# Sheet2.net
KiCad netlist of a schematic drawn in Altium Designer
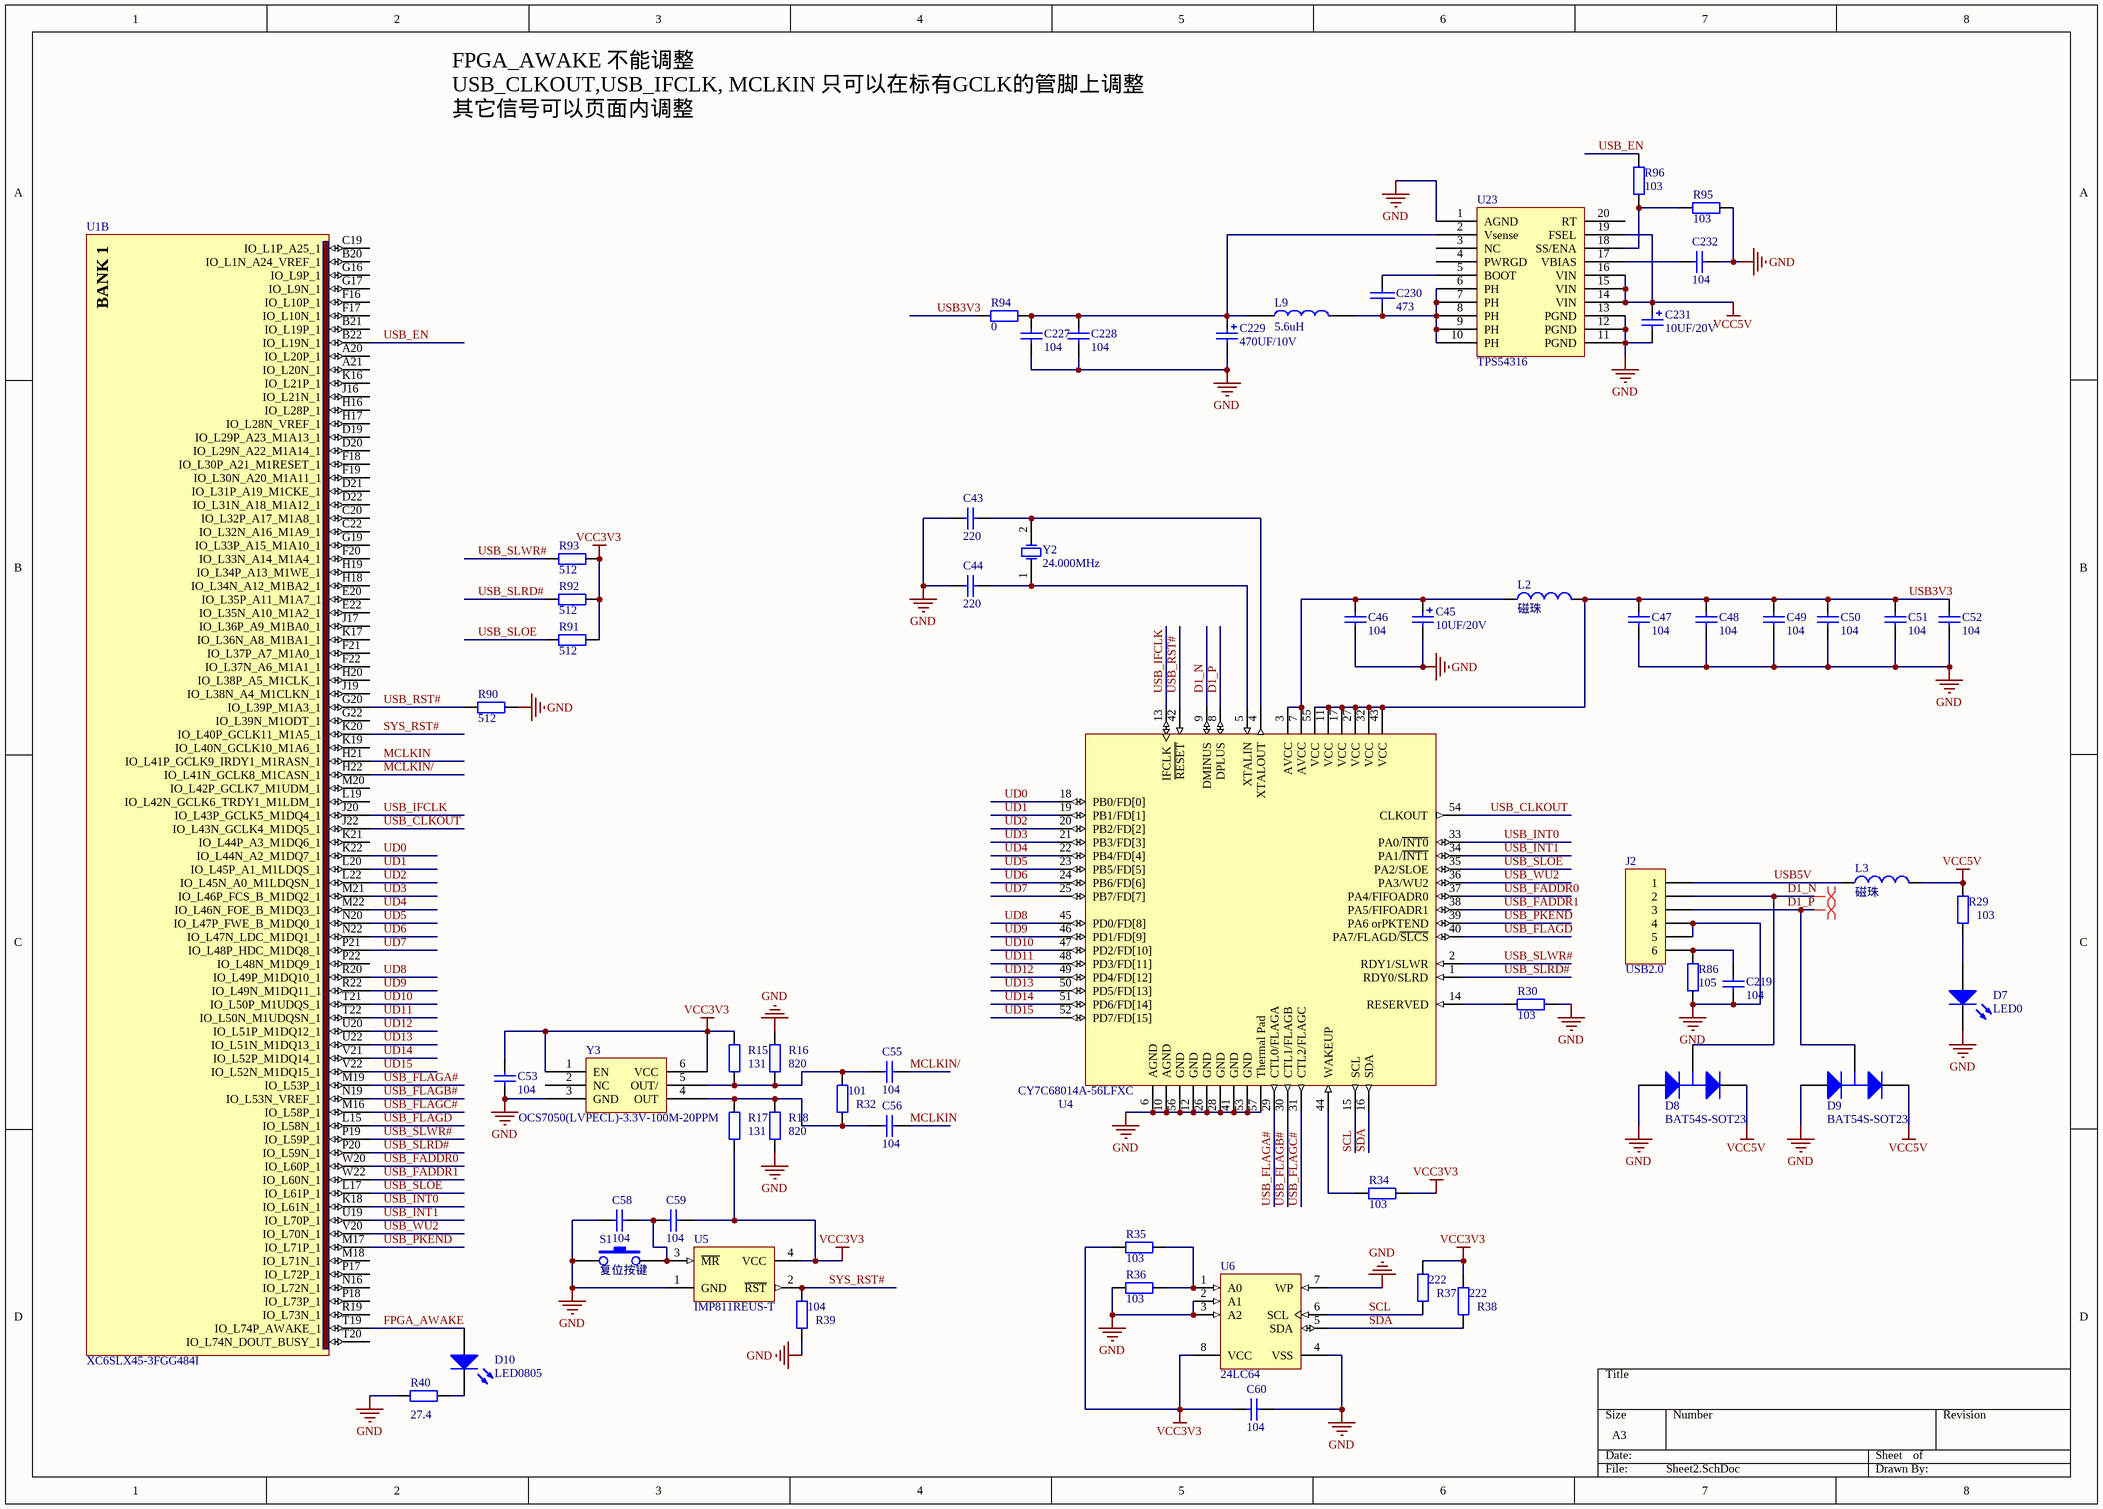
[diagram p0: Sheet2.SchDoc]

(export (version "E")
  (design (tool "Eeschema 10.0.6"))
  (components
    (comp (ref "C43")
      (value "220")
      (footprint "0402")
      (description "Capacitor")
      (fields (field (name "PUBLISHER") "Altium Limited"))
      (libsource (lib "Miscellaneous Devices") (part "Cap"))
    )
    (comp (ref "C44")
      (value "220")
      (footprint "0402")
      (description "Capacitor")
      (fields (field (name "PUBLISHER") "Altium Limited"))
      (libsource (lib "Miscellaneous Devices") (part "Cap"))
    )
    (comp (ref "C45")
      (value "10UF/20V")
      (footprint "CAP-B")
      (description "Polarized Capacitor (Axial)")
      (fields (field (name "PUBLISHER") "Altium Limited"))
      (libsource (lib "Miscellaneous Devices") (part "Cap Pol2"))
    )
    (comp (ref "C46")
      (value "104")
      (footprint "0402")
      (description "Capacitor")
      (fields (field (name "PUBLISHER") "Altium Limited"))
      (libsource (lib "Miscellaneous Devices") (part "Cap"))
    )
    (comp (ref "C47")
      (value "104")
      (footprint "0402")
      (description "Capacitor")
      (fields (field (name "PUBLISHER") "Altium Limited"))
      (libsource (lib "Miscellaneous Devices") (part "Cap"))
    )
    (comp (ref "C48")
      (value "104")
      (footprint "0402")
      (description "Capacitor")
      (fields (field (name "PUBLISHER") "Altium Limited"))
      (libsource (lib "Miscellaneous Devices") (part "Cap"))
    )
    (comp (ref "C49")
      (value "104")
      (footprint "0402")
      (description "Capacitor")
      (fields (field (name "PUBLISHER") "Altium Limited"))
      (libsource (lib "Miscellaneous Devices") (part "Cap"))
    )
    (comp (ref "C50")
      (value "104")
      (footprint "0402")
      (description "Capacitor")
      (fields (field (name "PUBLISHER") "Altium Limited"))
      (libsource (lib "Miscellaneous Devices") (part "Cap"))
    )
    (comp (ref "C51")
      (value "104")
      (footprint "0402")
      (description "Capacitor")
      (fields (field (name "PUBLISHER") "Altium Limited"))
      (libsource (lib "Miscellaneous Devices") (part "Cap"))
    )
    (comp (ref "C52")
      (value "104")
      (footprint "0402")
      (description "Capacitor")
      (fields (field (name "PUBLISHER") "Altium Limited"))
      (libsource (lib "Miscellaneous Devices") (part "Cap"))
    )
    (comp (ref "C53")
      (value "104")
      (footprint "0402")
      (description "Capacitor")
      (fields (field (name "PUBLISHER") "Altium Limited"))
      (libsource (lib "Miscellaneous Devices") (part "Cap"))
    )
    (comp (ref "C55")
      (value "104")
      (footprint "0402")
      (description "Capacitor")
      (fields (field (name "PUBLISHER") "Altium Limited"))
      (libsource (lib "Miscellaneous Devices") (part "Cap"))
    )
    (comp (ref "C56")
      (value "104")
      (footprint "0402")
      (description "Capacitor")
      (fields (field (name "PUBLISHER") "Altium Limited"))
      (libsource (lib "Miscellaneous Devices") (part "Cap"))
    )
    (comp (ref "C58")
      (value "104")
      (footprint "0402")
      (description "Capacitor")
      (fields (field (name "PUBLISHER") "Altium Limited"))
      (libsource (lib "Miscellaneous Devices") (part "Cap"))
    )
    (comp (ref "C59")
      (value "104")
      (footprint "0402")
      (description "Capacitor")
      (fields (field (name "PUBLISHER") "Altium Limited"))
      (libsource (lib "Miscellaneous Devices") (part "Cap"))
    )
    (comp (ref "C60")
      (value "104")
      (footprint "0402")
      (description "Capacitor")
      (fields (field (name "PUBLISHER") "Altium Limited"))
      (libsource (lib "Miscellaneous Devices") (part "Cap"))
    )
    (comp (ref "C219")
      (value "104")
      (footprint "0402")
      (description "Capacitor")
      (fields (field (name "PUBLISHER") "Altium Limited"))
      (libsource (lib "Miscellaneous Devices") (part "Cap"))
    )
    (comp (ref "C227")
      (value "104")
      (footprint "0402")
      (description "Capacitor")
      (fields (field (name "PUBLISHER") "Altium Limited"))
      (libsource (lib "Miscellaneous Devices") (part "Cap"))
    )
    (comp (ref "C228")
      (value "104")
      (footprint "0402")
      (description "Capacitor")
      (fields (field (name "PUBLISHER") "Altium Limited"))
      (libsource (lib "Miscellaneous Devices") (part "Cap"))
    )
    (comp (ref "C229")
      (value "470UF/10V")
      (footprint "CAP-D")
      (description "Polarized Capacitor (Axial)")
      (fields (field (name "PUBLISHER") "Altium Limited"))
      (libsource (lib "Miscellaneous Devices") (part "Cap Pol2"))
    )
    (comp (ref "C230")
      (value "473")
      (footprint "0402")
      (description "Capacitor")
      (libsource (lib "*") (part "CAP"))
    )
    (comp (ref "C231")
      (value "10UF/20V")
      (footprint "CAP-B")
      (description "Polarized Capacitor (Axial)")
      (fields (field (name "PUBLISHER") "Altium Limited"))
      (libsource (lib "Miscellaneous Devices") (part "Cap Pol2"))
    )
    (comp (ref "C232")
      (value "104")
      (footprint "0402")
      (description "Capacitor")
      (fields (field (name "PUBLISHER") "Altium Limited"))
      (libsource (lib "Miscellaneous Devices") (part "Cap"))
    )
    (comp (ref "D7")
      (value "LED0")
      (footprint "0805LED")
      (description "Typical INFRARED GaAs LED")
      (fields (field (name "PUBLISHER") "Altium Limited"))
      (libsource (lib "Miscellaneous Devices") (part "LED0"))
    )
    (comp (ref "D8")
      (value "BAT54S-SOT23")
      (footprint "SOT23-3L")
      (description "Silicon Switching Diode Array for High-Speed Switching")
      (fields (field (name "PUBLISHER") "Altium Limited"))
      (libsource (lib "Infineon Discrete Diode") (part "BAV99"))
    )
    (comp (ref "D9")
      (value "BAT54S-SOT23")
      (footprint "SOT23-3L")
      (description "Silicon Switching Diode Array for High-Speed Switching")
      (fields (field (name "PUBLISHER") "Altium Limited"))
      (libsource (lib "Infineon Discrete Diode") (part "BAV99"))
    )
    (comp (ref "D10")
      (value "LED0805")
      (footprint "0805LED")
      (description "Typical INFRARED GaAs LED")
      (fields (field (name "PUBLISHER") "Altium Limited"))
      (libsource (lib "Miscellaneous Devices") (part "LED0"))
    )
    (comp (ref "J2")
      (value "USB2.0")
      (footprint "USB/SM0.8-6H5")
      (description "Header, 6-Pin")
      (fields (field (name "PUBLISHER") "Altium Limited"))
      (libsource (lib "Miscellaneous Connectors") (part "Header 6"))
    )
    (comp (ref "L2")
      (value "磁珠")
      (footprint "1206A")
      (description "Inductor")
      (fields (field (name "PUBLISHER") "Altium Limited"))
      (libsource (lib "Miscellaneous Devices") (part "Inductor"))
    )
    (comp (ref "L3")
      (value "磁珠")
      (footprint "1206A")
      (description "Inductor")
      (fields (field (name "PUBLISHER") "Altium Limited"))
      (libsource (lib "Miscellaneous Devices") (part "Inductor"))
    )
    (comp (ref "L9") (value "5.6uH") (footprint "L5R2") (libsource (lib "*") (part "INDUCTOR1")))
    (comp (ref "R15")
      (value "131")
      (footprint "0603")
      (description "Resistor")
      (fields (field (name "PUBLISHER") "Altium Limited"))
      (libsource (lib "") (part "Res2_1"))
    )
    (comp (ref "R16")
      (value "820")
      (footprint "0603")
      (description "Resistor")
      (fields (field (name "PUBLISHER") "Altium Limited"))
      (libsource (lib "") (part "Res2_1"))
    )
    (comp (ref "R17")
      (value "131")
      (footprint "0603")
      (description "Resistor")
      (fields (field (name "PUBLISHER") "Altium Limited"))
      (libsource (lib "") (part "Res2_1"))
    )
    (comp (ref "R18")
      (value "820")
      (footprint "0603")
      (description "Resistor")
      (fields (field (name "PUBLISHER") "Altium Limited"))
      (libsource (lib "") (part "Res2_1"))
    )
    (comp (ref "R29")
      (value "103")
      (footprint "0603")
      (description "Resistor")
      (fields (field (name "PUBLISHER") "Altium Limited"))
      (libsource (lib "") (part "Res2_1"))
    )
    (comp (ref "R30")
      (value "103")
      (footprint "0603")
      (description "Resistor")
      (fields (field (name "PUBLISHER") "Altium Limited"))
      (libsource (lib "") (part "Res2_2"))
    )
    (comp (ref "R32")
      (value "101")
      (footprint "0603")
      (description "Resistor")
      (fields (field (name "PUBLISHER") "Altium Limited"))
      (libsource (lib "") (part "Res2_1"))
    )
    (comp (ref "R34")
      (value "103")
      (footprint "0603")
      (description "Resistor")
      (fields (field (name "PUBLISHER") "Altium Limited"))
      (libsource (lib "Miscellaneous Devices") (part "Res2"))
    )
    (comp (ref "R35")
      (value "103")
      (footprint "0603")
      (description "Resistor")
      (fields (field (name "PUBLISHER") "Altium Limited"))
      (libsource (lib "Miscellaneous Devices") (part "Res2"))
    )
    (comp (ref "R36")
      (value "103")
      (footprint "0603")
      (description "Resistor")
      (fields (field (name "PUBLISHER") "Altium Limited"))
      (libsource (lib "Miscellaneous Devices") (part "Res2"))
    )
    (comp (ref "R37")
      (value "222")
      (footprint "0603")
      (description "Resistor")
      (fields (field (name "PUBLISHER") "Altium Limited"))
      (libsource (lib "") (part "Res2_3"))
    )
    (comp (ref "R38")
      (value "222")
      (footprint "0603")
      (description "Resistor")
      (fields (field (name "PUBLISHER") "Altium Limited"))
      (libsource (lib "") (part "Res2_3"))
    )
    (comp (ref "R39")
      (value "104")
      (footprint "0603")
      (description "Resistor")
      (fields (field (name "PUBLISHER") "Altium Limited"))
      (libsource (lib "") (part "Res2_1"))
    )
    (comp (ref "R40")
      (value "27.4")
      (footprint "0603")
      (description "Resistor")
      (fields (field (name "PUBLISHER") "Altium Limited"))
      (libsource (lib "") (part "Res2_2"))
    )
    (comp (ref "R86")
      (value "105")
      (footprint "0603")
      (description "Resistor")
      (fields (field (name "PUBLISHER") "Altium Limited"))
      (libsource (lib "") (part "Res2_1"))
    )
    (comp (ref "R90")
      (value "512")
      (footprint "0603")
      (description "Resistor")
      (fields (field (name "PUBLISHER") "Altium Limited"))
      (libsource (lib "Miscellaneous Devices") (part "Res2"))
    )
    (comp (ref "R91")
      (value "512")
      (footprint "0603")
      (description "Resistor")
      (fields (field (name "PUBLISHER") "Altium Limited"))
      (libsource (lib "Miscellaneous Devices") (part "Res2"))
    )
    (comp (ref "R92")
      (value "512")
      (footprint "0603")
      (description "Resistor")
      (fields (field (name "PUBLISHER") "Altium Limited"))
      (libsource (lib "Miscellaneous Devices") (part "Res2"))
    )
    (comp (ref "R93")
      (value "512")
      (footprint "0603")
      (description "Resistor")
      (fields (field (name "PUBLISHER") "Altium Limited"))
      (libsource (lib "Miscellaneous Devices") (part "Res2"))
    )
    (comp (ref "R94")
      (value "0")
      (footprint "0603")
      (description "Resistor")
      (fields (field (name "PUBLISHER") "Altium Limited"))
      (libsource (lib "Miscellaneous Devices") (part "Res2"))
    )
    (comp (ref "R95")
      (value "103")
      (footprint "0603")
      (description "Resistor")
      (fields (field (name "PUBLISHER") "Altium Limited"))
      (libsource (lib "Miscellaneous Devices") (part "Res2"))
    )
    (comp (ref "R96")
      (value "103")
      (footprint "0603")
      (description "Resistor")
      (fields (field (name "PUBLISHER") "Altium Limited"))
      (libsource (lib "") (part "Res2_3"))
    )
    (comp (ref "S1") (value "复位按键") (footprint "RESETKEY") (libsource (lib "*") (part "SW-PB")))
    (comp (ref "U1")
      (value "XC6SLX45-3FGG484I")
      (footprint "FGG484")
      (fields (field (name "PUBLISHER") "Altium Limited"))
      (libsource (lib "Xilinx Spartan-6") (part "XC6SLX45-3FGG484I"))
    )
    (comp (ref "U4")
      (value "CY7C68014A-56LFXC")
      (footprint "LF56A_N")
      (fields (field (name "PUBLISHER") "Altium Limited"))
      (libsource (lib "Cypress USB High-Speed") (part "CY7C68014A-56LFXC"))
    )
    (comp (ref "U5")
      (value "IMP811REUS-T")
      (footprint "SOT-143")
      (description "4-Pin µP Voltage Monitors with Manual Reset Input")
      (fields (field (name "PUBLISHER") "Altium Limited"))
      (libsource (lib "Maxim Power Mgt Supervisory Circuit") (part "MAX811-EUS-T"))
    )
    (comp (ref "U6")
      (value "24LC64")
      (footprint "SMD8XX")
      (description "2Kbit, 400kHz, 2.5V, I2C Serial EEPROM, 8-Pin SOIC 150mil, Industrial Temperature")
      (fields (field (name "PUBLISHER") "Altium Limited"))
      (libsource (lib "Microchip Memory I2C Serial EEPROM") (part "24LC02B-I/SN"))
    )
    (comp (ref "U23")
      (value "TPS54316")
      (footprint "SOP20")
      (description "TPS54312")
      (libsource (lib "*") (part "TPS54312"))
    )
    (comp (ref "Y2")
      (value "24.000MHz")
      (footprint "CRYSTAL_2")
      (description "Crystal Oscillator")
      (fields (field (name "PUBLISHER") "Altium Limited"))
      (libsource (lib "Miscellaneous Devices") (part "XTAL"))
    )
    (comp (ref "Y3")
      (value "OCS7050(LVPECL)-3.3V-100M-20PPM")
      (footprint "100M_diff")
      (libsource (lib "Schlib1") (part "Component_1"))
    )
  )
  (nets
    (net (code "1") (name "/D1_N") (class "Default")
      (node (ref "D8") (pin "3") (pinfunction "C_3") (pintype "passive"))
      (node (ref "J2") (pin "2") (pinfunction "2_2") (pintype "passive"))
      (node (ref "U4") (pin "9") (pinfunction "DMINUS_9") (pintype "bidirectional"))
    )
    (net (code "2") (name "/D1_P") (class "Default")
      (node (ref "D9") (pin "3") (pinfunction "C_3") (pintype "passive"))
      (node (ref "J2") (pin "3") (pinfunction "3_3") (pintype "passive"))
      (node (ref "U4") (pin "8") (pinfunction "DPLUS_8") (pintype "bidirectional"))
    )
    (net (code "3") (name "/FPGA_AWAKE") (class "Default")
      (node (ref "D10") (pin "1") (pinfunction "A_1") (pintype "passive"))
      (node (ref "U1") (pin "T19") (pinfunction "IO_L74P_AWAKE_1_T19") (pintype "bidirectional"))
    )
    (net (code "4") (name "/MCLKIN") (class "Default")
      (node (ref "C56") (pin "2") (pinfunction "2_2") (pintype "passive"))
      (node (ref "U1") (pin "H21") (pinfunction "IO_L41P_GCLK9_IRDY1_M1RASN_1_H21") (pintype "bidirectional"))
    )
    (net (code "5") (name "/MCLKIN{slash}") (class "Default")
      (node (ref "C55") (pin "2") (pinfunction "2_2") (pintype "passive"))
      (node (ref "U1") (pin "H22") (pinfunction "IO_L41N_GCLK8_M1CASN_1_H22") (pintype "bidirectional"))
    )
    (net (code "6") (name "/SCL") (class "Default")
      (node (ref "R37") (pin "2") (pinfunction "2_2") (pintype "passive"))
      (node (ref "U4") (pin "15") (pinfunction "SCL_15") (pintype "output"))
      (node (ref "U6") (pin "6") (pinfunction "SCL_6") (pintype "input"))
    )
    (net (code "7") (name "/SDA") (class "Default")
      (node (ref "R38") (pin "2") (pinfunction "2_2") (pintype "passive"))
      (node (ref "U4") (pin "16") (pinfunction "SDA_16") (pintype "output"))
      (node (ref "U6") (pin "5") (pinfunction "SDA_5") (pintype "bidirectional"))
    )
    (net (code "8") (name "/SYS_RST#") (class "Default")
      (node (ref "R39") (pin "2") (pinfunction "2_2") (pintype "passive"))
      (node (ref "U1") (pin "K20") (pinfunction "IO_L40P_GCLK11_M1A5_1_K20") (pintype "bidirectional"))
      (node (ref "U5") (pin "2") (pinfunction "~{RST}_2") (pintype "output"))
    )
    (net (code "9") (name "/UD0") (class "Default")
      (node (ref "U1") (pin "K22") (pinfunction "IO_L44N_A2_M1DQ7_1_K22") (pintype "bidirectional"))
      (node (ref "U4") (pin "18") (pinfunction "PB0/FD[0]_18") (pintype "bidirectional"))
    )
    (net (code "10") (name "/UD1") (class "Default")
      (node (ref "U1") (pin "L20") (pinfunction "IO_L45P_A1_M1LDQS_1_L20") (pintype "bidirectional"))
      (node (ref "U4") (pin "19") (pinfunction "PB1/FD[1]_19") (pintype "bidirectional"))
    )
    (net (code "11") (name "/UD2") (class "Default")
      (node (ref "U1") (pin "L22") (pinfunction "IO_L45N_A0_M1LDQSN_1_L22") (pintype "bidirectional"))
      (node (ref "U4") (pin "20") (pinfunction "PB2/FD[2]_20") (pintype "bidirectional"))
    )
    (net (code "12") (name "/UD3") (class "Default")
      (node (ref "U1") (pin "M21") (pinfunction "IO_L46P_FCS_B_M1DQ2_1_M21") (pintype "bidirectional"))
      (node (ref "U4") (pin "21") (pinfunction "PB3/FD[3]_21") (pintype "bidirectional"))
    )
    (net (code "13") (name "/UD4") (class "Default")
      (node (ref "U1") (pin "M22") (pinfunction "IO_L46N_FOE_B_M1DQ3_1_M22") (pintype "bidirectional"))
      (node (ref "U4") (pin "22") (pinfunction "PB4/FD[4]_22") (pintype "bidirectional"))
    )
    (net (code "14") (name "/UD5") (class "Default")
      (node (ref "U1") (pin "N20") (pinfunction "IO_L47P_FWE_B_M1DQ0_1_N20") (pintype "bidirectional"))
      (node (ref "U4") (pin "23") (pinfunction "PB5/FD[5]_23") (pintype "bidirectional"))
    )
    (net (code "15") (name "/UD6") (class "Default")
      (node (ref "U1") (pin "N22") (pinfunction "IO_L47N_LDC_M1DQ1_1_N22") (pintype "bidirectional"))
      (node (ref "U4") (pin "24") (pinfunction "PB6/FD[6]_24") (pintype "bidirectional"))
    )
    (net (code "16") (name "/UD7") (class "Default")
      (node (ref "U1") (pin "P21") (pinfunction "IO_L48P_HDC_M1DQ8_1_P21") (pintype "bidirectional"))
      (node (ref "U4") (pin "25") (pinfunction "PB7/FD[7]_25") (pintype "bidirectional"))
    )
    (net (code "17") (name "/UD8") (class "Default")
      (node (ref "U1") (pin "R20") (pinfunction "IO_L49P_M1DQ10_1_R20") (pintype "bidirectional"))
      (node (ref "U4") (pin "45") (pinfunction "PD0/FD[8]_45") (pintype "bidirectional"))
    )
    (net (code "18") (name "/UD9") (class "Default")
      (node (ref "U1") (pin "R22") (pinfunction "IO_L49N_M1DQ11_1_R22") (pintype "bidirectional"))
      (node (ref "U4") (pin "46") (pinfunction "PD1/FD[9]_46") (pintype "bidirectional"))
    )
    (net (code "19") (name "/UD10") (class "Default")
      (node (ref "U1") (pin "T21") (pinfunction "IO_L50P_M1UDQS_1_T21") (pintype "bidirectional"))
      (node (ref "U4") (pin "47") (pinfunction "PD2/FD[10]_47") (pintype "bidirectional"))
    )
    (net (code "20") (name "/UD11") (class "Default")
      (node (ref "U1") (pin "T22") (pinfunction "IO_L50N_M1UDQSN_1_T22") (pintype "bidirectional"))
      (node (ref "U4") (pin "48") (pinfunction "PD3/FD[11]_48") (pintype "bidirectional"))
    )
    (net (code "21") (name "/UD12") (class "Default")
      (node (ref "U1") (pin "U20") (pinfunction "IO_L51P_M1DQ12_1_U20") (pintype "bidirectional"))
      (node (ref "U4") (pin "49") (pinfunction "PD4/FD[12]_49") (pintype "bidirectional"))
    )
    (net (code "22") (name "/UD13") (class "Default")
      (node (ref "U1") (pin "U22") (pinfunction "IO_L51N_M1DQ13_1_U22") (pintype "bidirectional"))
      (node (ref "U4") (pin "50") (pinfunction "PD5/FD[13]_50") (pintype "bidirectional"))
    )
    (net (code "23") (name "/UD14") (class "Default")
      (node (ref "U1") (pin "V21") (pinfunction "IO_L52P_M1DQ14_1_V21") (pintype "bidirectional"))
      (node (ref "U4") (pin "51") (pinfunction "PD6/FD[14]_51") (pintype "bidirectional"))
    )
    (net (code "24") (name "/UD15") (class "Default")
      (node (ref "U1") (pin "V22") (pinfunction "IO_L52N_M1DQ15_1_V22") (pintype "bidirectional"))
      (node (ref "U4") (pin "52") (pinfunction "PD7/FD[15]_52") (pintype "bidirectional"))
    )
    (net (code "25") (name "/USB3V3") (class "Default")
      (node (ref "C47") (pin "2") (pinfunction "2_2") (pintype "passive"))
      (node (ref "C48") (pin "2") (pinfunction "2_2") (pintype "passive"))
      (node (ref "C49") (pin "2") (pinfunction "2_2") (pintype "passive"))
      (node (ref "C50") (pin "2") (pinfunction "2_2") (pintype "passive"))
      (node (ref "C51") (pin "2") (pinfunction "2_2") (pintype "passive"))
      (node (ref "C52") (pin "2") (pinfunction "2_2") (pintype "passive"))
      (node (ref "L2") (pin "2") (pinfunction "2_2") (pintype "passive"))
      (node (ref "R94") (pin "2") (pinfunction "2_2") (pintype "passive"))
      (node (ref "U4") (pin "11") (pinfunction "VCC_11") (pintype "power_in"))
      (node (ref "U4") (pin "17") (pinfunction "VCC_17") (pintype "power_in"))
      (node (ref "U4") (pin "27") (pinfunction "VCC_27") (pintype "power_in"))
      (node (ref "U4") (pin "32") (pinfunction "VCC_32") (pintype "power_in"))
      (node (ref "U4") (pin "43") (pinfunction "VCC_43") (pintype "power_in"))
      (node (ref "U4") (pin "55") (pinfunction "VCC_55") (pintype "power_in"))
    )
    (net (code "26") (name "/USB5V") (class "Default")
      (node (ref "J2") (pin "1") (pinfunction "1_1") (pintype "passive"))
      (node (ref "L3") (pin "1") (pinfunction "1_1") (pintype "passive"))
    )
    (net (code "27") (name "/USB_CLKOUT") (class "Default")
      (node (ref "U1") (pin "J22") (pinfunction "IO_L43N_GCLK4_M1DQ5_1_J22") (pintype "bidirectional"))
      (node (ref "U4") (pin "54") (pinfunction "CLKOUT_54") (pintype "output"))
    )
    (net (code "28") (name "/USB_EN") (class "Default")
      (node (ref "R96") (pin "1") (pinfunction "1_1") (pintype "passive"))
      (node (ref "U1") (pin "B22") (pinfunction "IO_L19N_1_B22") (pintype "bidirectional"))
    )
    (net (code "29") (name "/USB_FADDR0") (class "Default")
      (node (ref "U1") (pin "W20") (pinfunction "IO_L60P_1_W20") (pintype "bidirectional"))
      (node (ref "U4") (pin "37") (pinfunction "PA4/FIFOADR0_37") (pintype "bidirectional"))
    )
    (net (code "30") (name "/USB_FADDR1") (class "Default")
      (node (ref "U1") (pin "W22") (pinfunction "IO_L60N_1_W22") (pintype "bidirectional"))
      (node (ref "U4") (pin "38") (pinfunction "PA5/FIFOADR1_38") (pintype "bidirectional"))
    )
    (net (code "31") (name "/USB_FLAGA#") (class "Default")
      (node (ref "U1") (pin "M19") (pinfunction "IO_L53P_1_M19") (pintype "bidirectional"))
      (node (ref "U4") (pin "29") (pinfunction "CTL0/FLAGA_29") (pintype "output"))
    )
    (net (code "32") (name "/USB_FLAGB#") (class "Default")
      (node (ref "U1") (pin "N19") (pinfunction "IO_L53N_VREF_1_N19") (pintype "bidirectional"))
      (node (ref "U4") (pin "30") (pinfunction "CTL1/FLAGB_30") (pintype "output"))
    )
    (net (code "33") (name "/USB_FLAGC#") (class "Default")
      (node (ref "U1") (pin "M16") (pinfunction "IO_L58P_1_M16") (pintype "bidirectional"))
      (node (ref "U4") (pin "31") (pinfunction "CTL2/FLAGC_31") (pintype "output"))
    )
    (net (code "34") (name "/USB_FLAGD") (class "Default")
      (node (ref "U1") (pin "L15") (pinfunction "IO_L58N_1_L15") (pintype "bidirectional"))
      (node (ref "U4") (pin "40") (pinfunction "PA7/FLAGD/~{SLCS}_40") (pintype "bidirectional"))
    )
    (net (code "35") (name "/USB_IFCLK") (class "Default")
      (node (ref "U1") (pin "J20") (pinfunction "IO_L43P_GCLK5_M1DQ4_1_J20") (pintype "bidirectional"))
      (node (ref "U4") (pin "13") (pinfunction "IFCLK_13") (pintype "bidirectional"))
    )
    (net (code "36") (name "/USB_INT0") (class "Default")
      (node (ref "U1") (pin "K18") (pinfunction "IO_L61N_1_K18") (pintype "bidirectional"))
      (node (ref "U4") (pin "33") (pinfunction "PA0/~{INT0}_33") (pintype "bidirectional"))
    )
    (net (code "37") (name "/USB_INT1") (class "Default")
      (node (ref "U1") (pin "U19") (pinfunction "IO_L70P_1_U19") (pintype "bidirectional"))
      (node (ref "U4") (pin "34") (pinfunction "PA1/~{INT1}_34") (pintype "bidirectional"))
    )
    (net (code "38") (name "/USB_PKEND") (class "Default")
      (node (ref "U1") (pin "M17") (pinfunction "IO_L71P_1_M17") (pintype "bidirectional"))
      (node (ref "U4") (pin "39") (pinfunction "PA6_orPKTEND_39") (pintype "bidirectional"))
    )
    (net (code "39") (name "/USB_RST#") (class "Default")
      (node (ref "R90") (pin "2") (pinfunction "2_2") (pintype "passive"))
      (node (ref "U1") (pin "G20") (pinfunction "IO_L39P_M1A3_1_G20") (pintype "bidirectional"))
      (node (ref "U4") (pin "42") (pinfunction "~{RESET}_42") (pintype "input"))
    )
    (net (code "40") (name "/USB_SLOE") (class "Default")
      (node (ref "R91") (pin "2") (pinfunction "2_2") (pintype "passive"))
      (node (ref "U1") (pin "L17") (pinfunction "IO_L61P_1_L17") (pintype "bidirectional"))
      (node (ref "U4") (pin "35") (pinfunction "PA2/SLOE_35") (pintype "bidirectional"))
    )
    (net (code "41") (name "/USB_SLRD#") (class "Default")
      (node (ref "R92") (pin "2") (pinfunction "2_2") (pintype "passive"))
      (node (ref "U1") (pin "P20") (pinfunction "IO_L59N_1_P20") (pintype "bidirectional"))
      (node (ref "U4") (pin "1") (pinfunction "RDY0/SLRD_1") (pintype "input"))
    )
    (net (code "42") (name "/USB_SLWR#") (class "Default")
      (node (ref "R93") (pin "2") (pinfunction "2_2") (pintype "passive"))
      (node (ref "U1") (pin "P19") (pinfunction "IO_L59P_1_P19") (pintype "bidirectional"))
      (node (ref "U4") (pin "2") (pinfunction "RDY1/SLWR_2") (pintype "input"))
    )
    (net (code "43") (name "/USB_WU2") (class "Default")
      (node (ref "U1") (pin "V20") (pinfunction "IO_L70N_1_V20") (pintype "bidirectional"))
      (node (ref "U4") (pin "36") (pinfunction "PA3/WU2_36") (pintype "bidirectional"))
    )
    (net (code "44") (name "GND") (class "Default")
      (node (ref "C219") (pin "2") (pinfunction "2_2") (pintype "passive"))
      (node (ref "C227") (pin "1") (pinfunction "1_1") (pintype "passive"))
      (node (ref "C228") (pin "1") (pinfunction "1_1") (pintype "passive"))
      (node (ref "C229") (pin "2") (pinfunction "2_2") (pintype "passive"))
      (node (ref "C231") (pin "2") (pinfunction "2_2") (pintype "passive"))
      (node (ref "C232") (pin "1") (pinfunction "1_1") (pintype "passive"))
      (node (ref "C43") (pin "1") (pinfunction "1_1") (pintype "passive"))
      (node (ref "C44") (pin "1") (pinfunction "1_1") (pintype "passive"))
      (node (ref "C45") (pin "2") (pinfunction "2_2") (pintype "passive"))
      (node (ref "C46") (pin "1") (pinfunction "1_1") (pintype "passive"))
      (node (ref "C47") (pin "1") (pinfunction "1_1") (pintype "passive"))
      (node (ref "C48") (pin "1") (pinfunction "1_1") (pintype "passive"))
      (node (ref "C49") (pin "1") (pinfunction "1_1") (pintype "passive"))
      (node (ref "C50") (pin "1") (pinfunction "1_1") (pintype "passive"))
      (node (ref "C51") (pin "1") (pinfunction "1_1") (pintype "passive"))
      (node (ref "C52") (pin "1") (pinfunction "1_1") (pintype "passive"))
      (node (ref "C53") (pin "2") (pinfunction "2_2") (pintype "passive"))
      (node (ref "C58") (pin "2") (pinfunction "2_2") (pintype "passive"))
      (node (ref "C60") (pin "1") (pinfunction "1_1") (pintype "passive"))
      (node (ref "D7") (pin "2") (pinfunction "K_2") (pintype "passive"))
      (node (ref "D8") (pin "1") (pinfunction "A_1") (pintype "passive"))
      (node (ref "D9") (pin "1") (pinfunction "A_1") (pintype "passive"))
      (node (ref "J2") (pin "4") (pinfunction "4_4") (pintype "passive"))
      (node (ref "J2") (pin "5") (pinfunction "5_5") (pintype "passive"))
      (node (ref "R16") (pin "2") (pinfunction "2_2") (pintype "passive"))
      (node (ref "R18") (pin "1") (pinfunction "1_1") (pintype "passive"))
      (node (ref "R30") (pin "2") (pinfunction "2_2") (pintype "passive"))
      (node (ref "R36") (pin "2") (pinfunction "2_2") (pintype "passive"))
      (node (ref "R39") (pin "1") (pinfunction "1_1") (pintype "passive"))
      (node (ref "R40") (pin "1") (pinfunction "1_1") (pintype "passive"))
      (node (ref "R86") (pin "1") (pinfunction "1_1") (pintype "passive"))
      (node (ref "R90") (pin "1") (pinfunction "1_1") (pintype "passive"))
      (node (ref "R95") (pin "1") (pinfunction "1_1") (pintype "passive"))
      (node (ref "S1") (pin "1") (pinfunction "1_1") (pintype "passive"))
      (node (ref "U23") (pin "1") (pinfunction "AGND_1") (pintype "passive"))
      (node (ref "U23") (pin "11") (pinfunction "PGND_11") (pintype "passive"))
      (node (ref "U23") (pin "12") (pinfunction "PGND_12") (pintype "passive"))
      (node (ref "U23") (pin "13") (pinfunction "PGND_13") (pintype "passive"))
      (node (ref "U4") (pin "10") (pinfunction "AGND_10") (pintype "power_in"))
      (node (ref "U4") (pin "12") (pinfunction "GND_12") (pintype "power_in"))
      (node (ref "U4") (pin "26") (pinfunction "GND_26") (pintype "power_in"))
      (node (ref "U4") (pin "28") (pinfunction "GND_28") (pintype "power_in"))
      (node (ref "U4") (pin "41") (pinfunction "GND_41") (pintype "power_in"))
      (node (ref "U4") (pin "53") (pinfunction "GND_53") (pintype "power_in"))
      (node (ref "U4") (pin "56") (pinfunction "GND_56") (pintype "power_in"))
      (node (ref "U4") (pin "57") (pinfunction "Thermal_Pad_57") (pintype "power_in"))
      (node (ref "U4") (pin "6") (pinfunction "AGND_6") (pintype "power_in"))
      (node (ref "U5") (pin "1") (pinfunction "GND_1") (pintype "power_in"))
      (node (ref "U6") (pin "2") (pinfunction "A1_2") (pintype "input"))
      (node (ref "U6") (pin "3") (pinfunction "A2_3") (pintype "input"))
      (node (ref "U6") (pin "4") (pinfunction "VSS_4") (pintype "power_in"))
      (node (ref "U6") (pin "7") (pinfunction "WP_7") (pintype "input"))
      (node (ref "Y3") (pin "3") (pinfunction "GND_3") (pintype "passive"))
    )
    (net (code "45") (name "Net-(C45-Pad1)") (class "Default")
      (node (ref "C45") (pin "1") (pinfunction "1_1") (pintype "passive"))
      (node (ref "C46") (pin "2") (pinfunction "2_2") (pintype "passive"))
      (node (ref "L2") (pin "1") (pinfunction "1_1") (pintype "passive"))
      (node (ref "U4") (pin "3") (pinfunction "AVCC_3") (pintype "power_in"))
      (node (ref "U4") (pin "7") (pinfunction "AVCC_7") (pintype "power_in"))
    )
    (net (code "46") (name "Net-(C219-Pad1)") (class "Default")
      (node (ref "C219") (pin "1") (pinfunction "1_1") (pintype "passive"))
      (node (ref "J2") (pin "6") (pinfunction "6_6") (pintype "passive"))
      (node (ref "R86") (pin "2") (pinfunction "2_2") (pintype "passive"))
    )
    (net (code "47") (name "Net-(C230-Pad1)") (class "Default")
      (node (ref "C230") (pin "1") (pinfunction "1_1") (pintype "passive"))
      (node (ref "L9") (pin "2") (pinfunction "2_2") (pintype "passive"))
      (node (ref "U23") (pin "10") (pinfunction "PH_10") (pintype "passive"))
      (node (ref "U23") (pin "6") (pinfunction "PH_6") (pintype "passive"))
      (node (ref "U23") (pin "7") (pinfunction "PH_7") (pintype "passive"))
      (node (ref "U23") (pin "8") (pinfunction "PH_8") (pintype "passive"))
      (node (ref "U23") (pin "9") (pinfunction "PH_9") (pintype "passive"))
    )
    (net (code "48") (name "Net-(D7-A)") (class "Default")
      (node (ref "D7") (pin "1") (pinfunction "A_1") (pintype "passive"))
      (node (ref "R29") (pin "1") (pinfunction "1_1") (pintype "passive"))
    )
    (net (code "49") (name "Net-(D10-K)") (class "Default")
      (node (ref "D10") (pin "2") (pinfunction "K_2") (pintype "passive"))
      (node (ref "R40") (pin "2") (pinfunction "2_2") (pintype "passive"))
    )
    (net (code "50") (name "Net-(U4-RESERVED)") (class "Default")
      (node (ref "R30") (pin "1") (pinfunction "1_1") (pintype "passive"))
      (node (ref "U4") (pin "14") (pinfunction "RESERVED_14") (pintype "input"))
    )
    (net (code "51") (name "Net-(U4-WAKEUP)") (class "Default")
      (node (ref "R34") (pin "2") (pinfunction "2_2") (pintype "passive"))
      (node (ref "U4") (pin "44") (pinfunction "WAKEUP_44") (pintype "input"))
    )
    (net (code "52") (name "Net-(U4-XTALIN)") (class "Default")
      (node (ref "C44") (pin "2") (pinfunction "2_2") (pintype "passive"))
      (node (ref "U4") (pin "5") (pinfunction "XTALIN_5") (pintype "input"))
      (node (ref "Y2") (pin "1") (pinfunction "OSC1_1") (pintype "passive"))
    )
    (net (code "53") (name "Net-(U4-XTALOUT)") (class "Default")
      (node (ref "C43") (pin "2") (pinfunction "2_2") (pintype "passive"))
      (node (ref "U4") (pin "4") (pinfunction "XTALOUT_4") (pintype "output"))
      (node (ref "Y2") (pin "2") (pinfunction "OSC2_2") (pintype "passive"))
    )
    (net (code "54") (name "Net-(U5-~{MR})") (class "Default")
      (node (ref "C58") (pin "1") (pinfunction "1_1") (pintype "passive"))
      (node (ref "C59") (pin "2") (pinfunction "2_2") (pintype "passive"))
      (node (ref "S1") (pin "2") (pinfunction "2_2") (pintype "passive"))
      (node (ref "U5") (pin "3") (pinfunction "~{MR}_3") (pintype "input"))
    )
    (net (code "55") (name "Net-(U6-A0)") (class "Default")
      (node (ref "R35") (pin "1") (pinfunction "1_1") (pintype "passive"))
      (node (ref "R36") (pin "1") (pinfunction "1_1") (pintype "passive"))
      (node (ref "U6") (pin "1") (pinfunction "A0_1") (pintype "input"))
    )
    (net (code "56") (name "Net-(U23-BOOT)") (class "Default")
      (node (ref "C230") (pin "2") (pinfunction "2_2") (pintype "passive"))
      (node (ref "U23") (pin "5") (pinfunction "BOOT_5") (pintype "passive"))
    )
    (net (code "57") (name "Net-(U23-SS{slash}ENA)") (class "Default")
      (node (ref "R95") (pin "2") (pinfunction "2_2") (pintype "passive"))
      (node (ref "R96") (pin "2") (pinfunction "2_2") (pintype "passive"))
      (node (ref "U23") (pin "18") (pinfunction "SS/ENA_18") (pintype "passive"))
    )
    (net (code "58") (name "Net-(U23-VBIAS)") (class "Default")
      (node (ref "C232") (pin "2") (pinfunction "2_2") (pintype "passive"))
      (node (ref "U23") (pin "17") (pinfunction "VBIAS_17") (pintype "passive"))
    )
    (net (code "59") (name "Net-(U23-Vsense)") (class "Default")
      (node (ref "C227") (pin "2") (pinfunction "2_2") (pintype "passive"))
      (node (ref "C228") (pin "2") (pinfunction "2_2") (pintype "passive"))
      (node (ref "C229") (pin "1") (pinfunction "1_1") (pintype "passive"))
      (node (ref "L9") (pin "1") (pinfunction "1_1") (pintype "passive"))
      (node (ref "R94") (pin "1") (pinfunction "1_1") (pintype "passive"))
      (node (ref "U23") (pin "2") (pinfunction "Vsense_2") (pintype "passive"))
    )
    (net (code "60") (name "Net-(Y3-OUT)") (class "Default")
      (node (ref "C56") (pin "1") (pinfunction "1_1") (pintype "passive"))
      (node (ref "R17") (pin "2") (pinfunction "2_2") (pintype "passive"))
      (node (ref "R18") (pin "2") (pinfunction "2_2") (pintype "passive"))
      (node (ref "R32") (pin "1") (pinfunction "1_1") (pintype "passive"))
      (node (ref "Y3") (pin "4") (pinfunction "OUT_4") (pintype "passive"))
    )
    (net (code "61") (name "Net-(Y3-OUT{slash})") (class "Default")
      (node (ref "C55") (pin "1") (pinfunction "1_1") (pintype "passive"))
      (node (ref "R15") (pin "1") (pinfunction "1_1") (pintype "passive"))
      (node (ref "R16") (pin "1") (pinfunction "1_1") (pintype "passive"))
      (node (ref "R32") (pin "2") (pinfunction "2_2") (pintype "passive"))
      (node (ref "Y3") (pin "5") (pinfunction "OUT/_5") (pintype "passive"))
    )
    (net (code "62") (name "VCC3V3") (class "Default")
      (node (ref "C53") (pin "1") (pinfunction "1_1") (pintype "passive"))
      (node (ref "C59") (pin "1") (pinfunction "1_1") (pintype "passive"))
      (node (ref "C60") (pin "2") (pinfunction "2_2") (pintype "passive"))
      (node (ref "R15") (pin "2") (pinfunction "2_2") (pintype "passive"))
      (node (ref "R17") (pin "1") (pinfunction "1_1") (pintype "passive"))
      (node (ref "R34") (pin "1") (pinfunction "1_1") (pintype "passive"))
      (node (ref "R35") (pin "2") (pinfunction "2_2") (pintype "passive"))
      (node (ref "R37") (pin "1") (pinfunction "1_1") (pintype "passive"))
      (node (ref "R38") (pin "1") (pinfunction "1_1") (pintype "passive"))
      (node (ref "R91") (pin "1") (pinfunction "1_1") (pintype "passive"))
      (node (ref "R92") (pin "1") (pinfunction "1_1") (pintype "passive"))
      (node (ref "R93") (pin "1") (pinfunction "1_1") (pintype "passive"))
      (node (ref "U5") (pin "4") (pinfunction "VCC_4") (pintype "power_in"))
      (node (ref "U6") (pin "8") (pinfunction "VCC_8") (pintype "power_in"))
      (node (ref "Y3") (pin "1") (pinfunction "EN_1") (pintype "passive"))
      (node (ref "Y3") (pin "6") (pinfunction "VCC_6") (pintype "passive"))
    )
    (net (code "63") (name "VCC5V") (class "Default")
      (node (ref "C231") (pin "1") (pinfunction "1_1") (pintype "passive"))
      (node (ref "D8") (pin "2") (pinfunction "K_2") (pintype "passive"))
      (node (ref "D9") (pin "2") (pinfunction "K_2") (pintype "passive"))
      (node (ref "L3") (pin "2") (pinfunction "2_2") (pintype "passive"))
      (node (ref "R29") (pin "2") (pinfunction "2_2") (pintype "passive"))
      (node (ref "U23") (pin "14") (pinfunction "VIN_14") (pintype "passive"))
      (node (ref "U23") (pin "15") (pinfunction "VIN_15") (pintype "passive"))
      (node (ref "U23") (pin "16") (pinfunction "VIN_16") (pintype "passive"))
      (node (ref "U23") (pin "19") (pinfunction "FSEL_19") (pintype "passive"))
    )
    (net (code "64") (name "unconnected-(U1B-IO_L1N_A24_VREF_1-PadB20)") (class "Default")
      (node (ref "U1") (pin "B20") (pinfunction "IO_L1N_A24_VREF_1_B20") (pintype "bidirectional"))
    )
    (net (code "65") (name "unconnected-(U1B-IO_L1P_A25_1-PadC19)") (class "Default")
      (node (ref "U1") (pin "C19") (pinfunction "IO_L1P_A25_1_C19") (pintype "bidirectional"))
    )
    (net (code "66") (name "unconnected-(U1B-IO_L9N_1-PadG17)") (class "Default")
      (node (ref "U1") (pin "G17") (pinfunction "IO_L9N_1_G17") (pintype "bidirectional"))
    )
    (net (code "67") (name "unconnected-(U1B-IO_L9P_1-PadG16)") (class "Default")
      (node (ref "U1") (pin "G16") (pinfunction "IO_L9P_1_G16") (pintype "bidirectional"))
    )
    (net (code "68") (name "unconnected-(U1B-IO_L10N_1-PadF17)") (class "Default")
      (node (ref "U1") (pin "F17") (pinfunction "IO_L10N_1_F17") (pintype "bidirectional"))
    )
    (net (code "69") (name "unconnected-(U1B-IO_L10P_1-PadF16)") (class "Default")
      (node (ref "U1") (pin "F16") (pinfunction "IO_L10P_1_F16") (pintype "bidirectional"))
    )
    (net (code "70") (name "unconnected-(U1B-IO_L19P_1-PadB21)") (class "Default")
      (node (ref "U1") (pin "B21") (pinfunction "IO_L19P_1_B21") (pintype "bidirectional"))
    )
    (net (code "71") (name "unconnected-(U1B-IO_L20N_1-PadA21)") (class "Default")
      (node (ref "U1") (pin "A21") (pinfunction "IO_L20N_1_A21") (pintype "bidirectional"))
    )
    (net (code "72") (name "unconnected-(U1B-IO_L20P_1-PadA20)") (class "Default")
      (node (ref "U1") (pin "A20") (pinfunction "IO_L20P_1_A20") (pintype "bidirectional"))
    )
    (net (code "73") (name "unconnected-(U1B-IO_L21N_1-PadJ16)") (class "Default")
      (node (ref "U1") (pin "J16") (pinfunction "IO_L21N_1_J16") (pintype "bidirectional"))
    )
    (net (code "74") (name "unconnected-(U1B-IO_L21P_1-PadK16)") (class "Default")
      (node (ref "U1") (pin "K16") (pinfunction "IO_L21P_1_K16") (pintype "bidirectional"))
    )
    (net (code "75") (name "unconnected-(U1B-IO_L28N_VREF_1-PadH17)") (class "Default")
      (node (ref "U1") (pin "H17") (pinfunction "IO_L28N_VREF_1_H17") (pintype "bidirectional"))
    )
    (net (code "76") (name "unconnected-(U1B-IO_L28P_1-PadH16)") (class "Default")
      (node (ref "U1") (pin "H16") (pinfunction "IO_L28P_1_H16") (pintype "bidirectional"))
    )
    (net (code "77") (name "unconnected-(U1B-IO_L29N_A22_M1A14_1-PadD20)") (class "Default")
      (node (ref "U1") (pin "D20") (pinfunction "IO_L29N_A22_M1A14_1_D20") (pintype "bidirectional"))
    )
    (net (code "78") (name "unconnected-(U1B-IO_L29P_A23_M1A13_1-PadD19)") (class "Default")
      (node (ref "U1") (pin "D19") (pinfunction "IO_L29P_A23_M1A13_1_D19") (pintype "bidirectional"))
    )
    (net (code "79") (name "unconnected-(U1B-IO_L30N_A20_M1A11_1-PadF19)") (class "Default")
      (node (ref "U1") (pin "F19") (pinfunction "IO_L30N_A20_M1A11_1_F19") (pintype "bidirectional"))
    )
    (net (code "80") (name "unconnected-(U1B-IO_L30P_A21_M1RESET_1-PadF18)") (class "Default")
      (node (ref "U1") (pin "F18") (pinfunction "IO_L30P_A21_M1RESET_1_F18") (pintype "bidirectional"))
    )
    (net (code "81") (name "unconnected-(U1B-IO_L31N_A18_M1A12_1-PadD22)") (class "Default")
      (node (ref "U1") (pin "D22") (pinfunction "IO_L31N_A18_M1A12_1_D22") (pintype "bidirectional"))
    )
    (net (code "82") (name "unconnected-(U1B-IO_L31P_A19_M1CKE_1-PadD21)") (class "Default")
      (node (ref "U1") (pin "D21") (pinfunction "IO_L31P_A19_M1CKE_1_D21") (pintype "bidirectional"))
    )
    (net (code "83") (name "unconnected-(U1B-IO_L32N_A16_M1A9_1-PadC22)") (class "Default")
      (node (ref "U1") (pin "C22") (pinfunction "IO_L32N_A16_M1A9_1_C22") (pintype "bidirectional"))
    )
    (net (code "84") (name "unconnected-(U1B-IO_L32P_A17_M1A8_1-PadC20)") (class "Default")
      (node (ref "U1") (pin "C20") (pinfunction "IO_L32P_A17_M1A8_1_C20") (pintype "bidirectional"))
    )
    (net (code "85") (name "unconnected-(U1B-IO_L33N_A14_M1A4_1-PadF20)") (class "Default")
      (node (ref "U1") (pin "F20") (pinfunction "IO_L33N_A14_M1A4_1_F20") (pintype "bidirectional"))
    )
    (net (code "86") (name "unconnected-(U1B-IO_L33P_A15_M1A10_1-PadG19)") (class "Default")
      (node (ref "U1") (pin "G19") (pinfunction "IO_L33P_A15_M1A10_1_G19") (pintype "bidirectional"))
    )
    (net (code "87") (name "unconnected-(U1B-IO_L34N_A12_M1BA2_1-PadH18)") (class "Default")
      (node (ref "U1") (pin "H18") (pinfunction "IO_L34N_A12_M1BA2_1_H18") (pintype "bidirectional"))
    )
    (net (code "88") (name "unconnected-(U1B-IO_L34P_A13_M1WE_1-PadH19)") (class "Default")
      (node (ref "U1") (pin "H19") (pinfunction "IO_L34P_A13_M1WE_1_H19") (pintype "bidirectional"))
    )
    (net (code "89") (name "unconnected-(U1B-IO_L35N_A10_M1A2_1-PadE22)") (class "Default")
      (node (ref "U1") (pin "E22") (pinfunction "IO_L35N_A10_M1A2_1_E22") (pintype "bidirectional"))
    )
    (net (code "90") (name "unconnected-(U1B-IO_L35P_A11_M1A7_1-PadE20)") (class "Default")
      (node (ref "U1") (pin "E20") (pinfunction "IO_L35P_A11_M1A7_1_E20") (pintype "bidirectional"))
    )
    (net (code "91") (name "unconnected-(U1B-IO_L36N_A8_M1BA1_1-PadK17)") (class "Default")
      (node (ref "U1") (pin "K17") (pinfunction "IO_L36N_A8_M1BA1_1_K17") (pintype "bidirectional"))
    )
    (net (code "92") (name "unconnected-(U1B-IO_L36P_A9_M1BA0_1-PadJ17)") (class "Default")
      (node (ref "U1") (pin "J17") (pinfunction "IO_L36P_A9_M1BA0_1_J17") (pintype "bidirectional"))
    )
    (net (code "93") (name "unconnected-(U1B-IO_L37N_A6_M1A1_1-PadF22)") (class "Default")
      (node (ref "U1") (pin "F22") (pinfunction "IO_L37N_A6_M1A1_1_F22") (pintype "bidirectional"))
    )
    (net (code "94") (name "unconnected-(U1B-IO_L37P_A7_M1A0_1-PadF21)") (class "Default")
      (node (ref "U1") (pin "F21") (pinfunction "IO_L37P_A7_M1A0_1_F21") (pintype "bidirectional"))
    )
    (net (code "95") (name "unconnected-(U1B-IO_L38N_A4_M1CLKN_1-PadJ19)") (class "Default")
      (node (ref "U1") (pin "J19") (pinfunction "IO_L38N_A4_M1CLKN_1_J19") (pintype "bidirectional"))
    )
    (net (code "96") (name "unconnected-(U1B-IO_L38P_A5_M1CLK_1-PadH20)") (class "Default")
      (node (ref "U1") (pin "H20") (pinfunction "IO_L38P_A5_M1CLK_1_H20") (pintype "bidirectional"))
    )
    (net (code "97") (name "unconnected-(U1B-IO_L39N_M1ODT_1-PadG22)") (class "Default")
      (node (ref "U1") (pin "G22") (pinfunction "IO_L39N_M1ODT_1_G22") (pintype "bidirectional"))
    )
    (net (code "98") (name "unconnected-(U1B-IO_L40N_GCLK10_M1A6_1-PadK19)") (class "Default")
      (node (ref "U1") (pin "K19") (pinfunction "IO_L40N_GCLK10_M1A6_1_K19") (pintype "bidirectional"))
    )
    (net (code "99") (name "unconnected-(U1B-IO_L42N_GCLK6_TRDY1_M1LDM_1-PadL19)") (class "Default")
      (node (ref "U1") (pin "L19") (pinfunction "IO_L42N_GCLK6_TRDY1_M1LDM_1_L19") (pintype "bidirectional"))
    )
    (net (code "100") (name "unconnected-(U1B-IO_L42P_GCLK7_M1UDM_1-PadM20)") (class "Default")
      (node (ref "U1") (pin "M20") (pinfunction "IO_L42P_GCLK7_M1UDM_1_M20") (pintype "bidirectional"))
    )
    (net (code "101") (name "unconnected-(U1B-IO_L44P_A3_M1DQ6_1-PadK21)") (class "Default")
      (node (ref "U1") (pin "K21") (pinfunction "IO_L44P_A3_M1DQ6_1_K21") (pintype "bidirectional"))
    )
    (net (code "102") (name "unconnected-(U1B-IO_L48N_M1DQ9_1-PadP22)") (class "Default")
      (node (ref "U1") (pin "P22") (pinfunction "IO_L48N_M1DQ9_1_P22") (pintype "bidirectional"))
    )
    (net (code "103") (name "unconnected-(U1B-IO_L71N_1-PadM18)") (class "Default")
      (node (ref "U1") (pin "M18") (pinfunction "IO_L71N_1_M18") (pintype "bidirectional"))
    )
    (net (code "104") (name "unconnected-(U1B-IO_L72N_1-PadN16)") (class "Default")
      (node (ref "U1") (pin "N16") (pinfunction "IO_L72N_1_N16") (pintype "bidirectional"))
    )
    (net (code "105") (name "unconnected-(U1B-IO_L72P_1-PadP17)") (class "Default")
      (node (ref "U1") (pin "P17") (pinfunction "IO_L72P_1_P17") (pintype "bidirectional"))
    )
    (net (code "106") (name "unconnected-(U1B-IO_L73N_1-PadR19)") (class "Default")
      (node (ref "U1") (pin "R19") (pinfunction "IO_L73N_1_R19") (pintype "bidirectional"))
    )
    (net (code "107") (name "unconnected-(U1B-IO_L73P_1-PadP18)") (class "Default")
      (node (ref "U1") (pin "P18") (pinfunction "IO_L73P_1_P18") (pintype "bidirectional"))
    )
    (net (code "108") (name "unconnected-(U1B-IO_L74N_DOUT_BUSY_1-PadT20)") (class "Default")
      (node (ref "U1") (pin "T20") (pinfunction "IO_L74N_DOUT_BUSY_1_T20") (pintype "bidirectional"))
    )
    (net (code "109") (name "unconnected-(U23-NC-Pad3)") (class "Default")
      (node (ref "U23") (pin "3") (pinfunction "NC_3") (pintype "passive"))
    )
    (net (code "110") (name "unconnected-(U23-PWRGD-Pad4)") (class "Default")
      (node (ref "U23") (pin "4") (pinfunction "PWRGD_4") (pintype "passive"))
    )
    (net (code "111") (name "unconnected-(U23-RT-Pad20)") (class "Default")
      (node (ref "U23") (pin "20") (pinfunction "RT_20") (pintype "passive"))
    )
    (net (code "112") (name "unconnected-(Y3-NC-Pad2)") (class "Default")
      (node (ref "Y3") (pin "2") (pinfunction "NC_2") (pintype "passive"))
    )
  )
)
